# logger_Chad.net
KiCad netlist of a schematic drawn in EAGLE
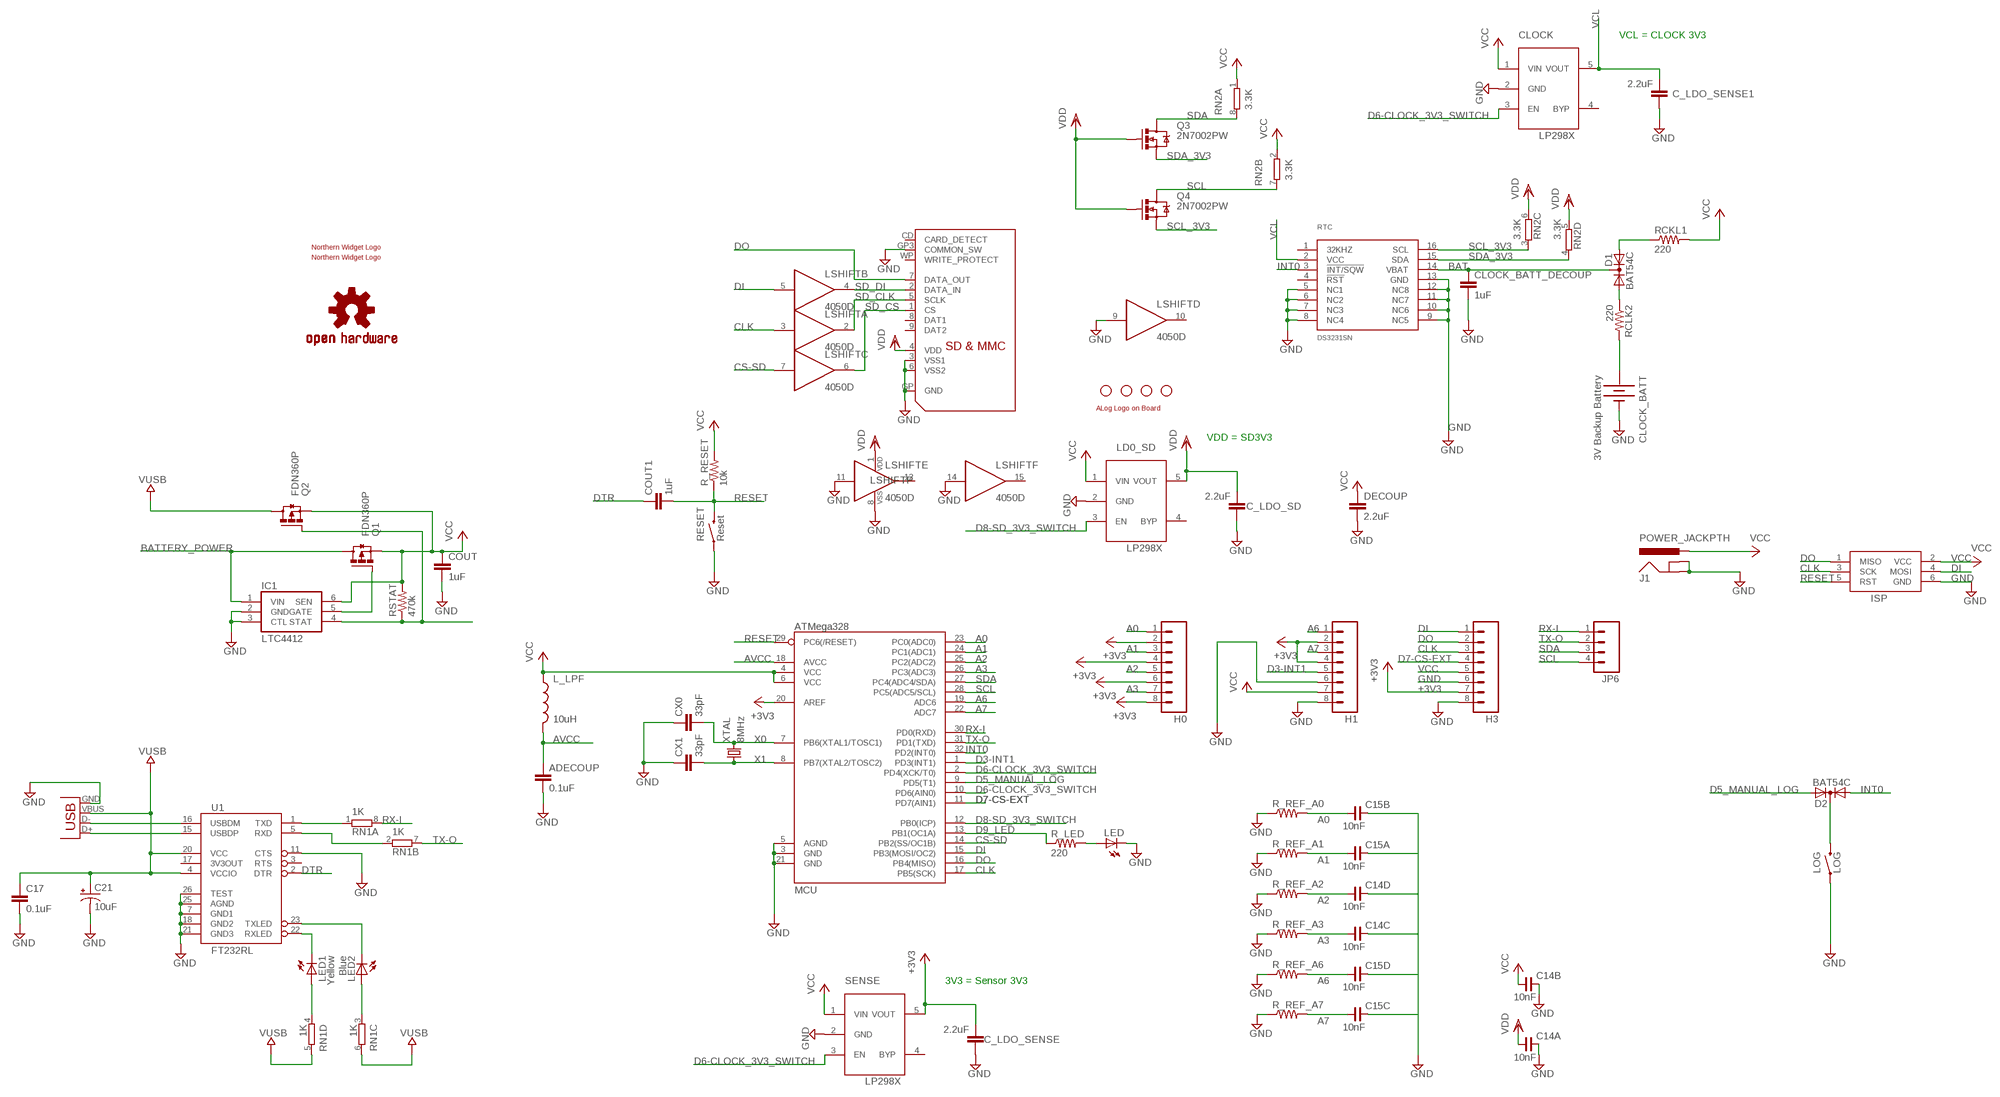
[diagram p0: schematic, sheet 1]

(export (version "E")
  (design (tool "Eeschema 10.0.6"))
  (components
    (comp (ref "ADECOUP")
      (value "0.1uF")
      (footprint "eagle-import:C0603")
      (libsource (lib "eagle-import") (part "resistor_C-EUC0603"))
    )
    (comp (ref "C14")
      (value "10nF")
      (footprint "eagle-import:CECJ-1206")
      (libsource (lib "eagle-import") (part "CCA_ECJ-1206"))
    )
    (comp (ref "C15")
      (value "10nF")
      (footprint "eagle-import:CECJ-1206")
      (libsource (lib "eagle-import") (part "CCA_ECJ-1206"))
    )
    (comp (ref "C17")
      (value "0.1uF")
      (footprint "eagle-import:C0603")
      (libsource (lib "eagle-import") (part "resistor_C-EUC0603"))
    )
    (comp (ref "C21")
      (value "10uF")
      (footprint "eagle-import:EIA3216")
      (libsource (lib "eagle-import") (part "CAP_POL1206"))
    )
    (comp (ref "CLOCK")
      (value "LP2985")
      (footprint "eagle-import:SOT23-5L")
      (libsource (lib "eagle-import") (part "LP298XS"))
    )
    (comp (ref "CLOCK_BATT")
      (value "3V Backup Battery")
      (footprint "eagle-import:BATTCON_12MM_PTH")
      (libsource (lib "eagle-import") (part "BATTERY12PTH"))
    )
    (comp (ref "CLOCK_BATT_DECOUP")
      (value "1uF")
      (footprint "eagle-import:C0603")
      (libsource (lib "eagle-import") (part "C-EUC0603"))
    )
    (comp (ref "COUT")
      (value "1uF")
      (footprint "eagle-import:C0603")
      (libsource (lib "eagle-import") (part "C-EUC0603"))
    )
    (comp (ref "COUT1")
      (value "1uF")
      (footprint "eagle-import:C0603")
      (libsource (lib "eagle-import") (part "C-EUC0603"))
    )
    (comp (ref "CX0")
      (value "33pF")
      (footprint "eagle-import:C0603")
      (libsource (lib "eagle-import") (part "resistor_C-EUC0603"))
    )
    (comp (ref "CX1")
      (value "33pF")
      (footprint "eagle-import:C0603")
      (libsource (lib "eagle-import") (part "resistor_C-EUC0603"))
    )
    (comp (ref "C_LDO_SD")
      (value "2.2uF")
      (footprint "eagle-import:C0603")
      (libsource (lib "eagle-import") (part "resistor_C-EUC0603"))
    )
    (comp (ref "C_LDO_SENSE")
      (value "2.2uF")
      (footprint "eagle-import:C0603")
      (libsource (lib "eagle-import") (part "resistor_C-EUC0603"))
    )
    (comp (ref "C_LDO_SENSE1")
      (value "2.2uF")
      (footprint "eagle-import:C0603")
      (libsource (lib "eagle-import") (part "resistor_C-EUC0603"))
    )
    (comp (ref "D1")
      (value "BAT54C")
      (footprint "eagle-import:SOT23C")
      (libsource (lib "eagle-import") (part "DIODE_AC-CA_"))
    )
    (comp (ref "D2")
      (value "BAT54C")
      (footprint "eagle-import:SOT23C")
      (libsource (lib "eagle-import") (part "DIODE_AC-CA_"))
    )
    (comp (ref "DECOUP")
      (value "2.2uF")
      (footprint "eagle-import:C0603")
      (libsource (lib "eagle-import") (part "resistor_C-EUC0603"))
    )
    (comp (ref "H0")
      (value "M083.5MM-8")
      (footprint "eagle-import:SCREWTERMINAL-3.5MM-8")
      (libsource (lib "eagle-import") (part "M083.5MM-8"))
    )
    (comp (ref "H1")
      (value "M083.5MM-8")
      (footprint "eagle-import:SCREWTERMINAL-3.5MM-8")
      (libsource (lib "eagle-import") (part "M083.5MM-8"))
    )
    (comp (ref "H3")
      (value "M083.5MM-8")
      (footprint "eagle-import:SCREWTERMINAL-3.5MM-8")
      (libsource (lib "eagle-import") (part "M083.5MM-8"))
    )
    (comp (ref "IC1")
      (value "LTC4412")
      (footprint "eagle-import:TSOT23-6")
      (libsource (lib "eagle-import") (part "LTC4412S6E"))
    )
    (comp (ref "ISP")
      (value "AVRISP-6")
      (footprint "eagle-import:AVRISP")
      (libsource (lib "eagle-import") (part "AVRISP-6"))
    )
    (comp (ref "J1")
      (value "POWER_JACKPTH")
      (footprint "eagle-import:POWER_JACK_PTH")
      (libsource (lib "eagle-import") (part "POWER_JACKPTH"))
    )
    (comp (ref "JP1")
      (value "STAND-OFF")
      (footprint "eagle-import:STAND-OFF")
      (libsource (lib "eagle-import") (part "STAND-OFF"))
    )
    (comp (ref "JP2")
      (value "STAND-OFF")
      (footprint "eagle-import:STAND-OFF")
      (libsource (lib "eagle-import") (part "STAND-OFF"))
    )
    (comp (ref "JP3")
      (value "STAND-OFF")
      (footprint "eagle-import:STAND-OFF")
      (libsource (lib "eagle-import") (part "STAND-OFF"))
    )
    (comp (ref "JP4")
      (value "STAND-OFF")
      (footprint "eagle-import:STAND-OFF")
      (libsource (lib "eagle-import") (part "STAND-OFF"))
    )
    (comp (ref "JP5")
      (value "USB-B")
      (footprint "eagle-import:USB-B-PTH")
      (libsource (lib "eagle-import") (part "USBPTH"))
    )
    (comp (ref "JP6")
      (value "M04SCREW")
      (footprint "eagle-import:SCREWTERMINAL-3.5MM-4")
      (libsource (lib "eagle-import") (part "M04SCREW"))
    )
    (comp (ref "LD0_SD")
      (value "LP2985")
      (footprint "eagle-import:SOT23-5L")
      (libsource (lib "eagle-import") (part "LP298XS"))
    )
    (comp (ref "LED")
      (value "LED3MM")
      (footprint "eagle-import:LED3MM")
      (libsource (lib "eagle-import") (part "LED3MM"))
    )
    (comp (ref "LED1")
      (value "Yellow")
      (footprint "eagle-import:LED-0603")
      (libsource (lib "eagle-import") (part "SparkFun-LED_LED0603"))
    )
    (comp (ref "LED2")
      (value "Blue")
      (footprint "eagle-import:LED-0603")
      (libsource (lib "eagle-import") (part "SparkFun-LED_LED0603"))
    )
    (comp (ref "LOG")
      (value "LOG")
      (footprint "eagle-import:TACTILE-PTH")
      (libsource (lib "eagle-import") (part "SWITCH-MOMENTARY-2PTH"))
    )
    (comp (ref "LOGO1")
      (value "OSHW-LOGOM")
      (footprint "eagle-import:OSHW-LOGO-M")
      (libsource (lib "eagle-import") (part "OSHW-LOGOM"))
    )
    (comp (ref "LSHIFT")
      (value "4050D")
      (footprint "eagle-import:SO16")
      (libsource (lib "eagle-import") (part "4050D"))
    )
    (comp (ref "L_LPF")
      (value "10uH")
      (footprint "eagle-import:0805")
      (libsource (lib "eagle-import") (part "INDUCTOR0805"))
    )
    (comp (ref "MCU")
      (value "ATMega328")
      (footprint "eagle-import:TQFP32-08")
      (libsource (lib "eagle-import") (part "ATMEGA168"))
    )
    (comp (ref "Q1")
      (value "FDN360P")
      (footprint "eagle-import:SUPER-SOT3")
      (libsource (lib "eagle-import") (part "FDN360P"))
    )
    (comp (ref "Q2")
      (value "FDN360P")
      (footprint "eagle-import:SUPER-SOT3")
      (libsource (lib "eagle-import") (part "FDN360P"))
    )
    (comp (ref "Q3")
      (value "2N7002PW")
      (footprint "eagle-import:SOT323")
      (libsource (lib "eagle-import") (part "MOSFET-NCHANNELSOT323"))
    )
    (comp (ref "Q4")
      (value "2N7002PW")
      (footprint "eagle-import:SOT323")
      (libsource (lib "eagle-import") (part "MOSFET-NCHANNELSOT323"))
    )
    (comp (ref "RCKL1")
      (value "220")
      (footprint "eagle-import:R0603")
      (libsource (lib "eagle-import") (part "R-US_R0603"))
    )
    (comp (ref "RCLK2")
      (value "220")
      (footprint "eagle-import:R0603")
      (libsource (lib "eagle-import") (part "R-US_R0603"))
    )
    (comp (ref "RESET")
      (value "Reset")
      (footprint "eagle-import:TACTILE-PTH")
      (libsource (lib "eagle-import") (part "SWITCH-MOMENTARY-2PTH"))
    )
    (comp (ref "RN1")
      (value "1K")
      (footprint "eagle-import:0603-ARC")
      (libsource (lib "eagle-import") (part "4R-N0603-ARC"))
    )
    (comp (ref "RN2")
      (value "3.3K")
      (footprint "eagle-import:0603-ARC")
      (libsource (lib "eagle-import") (part "4R-N0603-ARC"))
    )
    (comp (ref "RSTAT")
      (value "470k")
      (footprint "eagle-import:R0603")
      (libsource (lib "eagle-import") (part "R-US_R0603"))
    )
    (comp (ref "RTC")
      (value "DS3231SN")
      (footprint "eagle-import:SO16W")
      (libsource (lib "eagle-import") (part "DS3231SN"))
    )
    (comp (ref "R_LED")
      (value "220")
      (footprint "eagle-import:R0603")
      (libsource (lib "eagle-import") (part "resistor_R-US_R0603"))
    )
    (comp (ref "R_REF_A0")
      (value "R-US_0207/10")
      (footprint "eagle-import:0207_10")
      (libsource (lib "eagle-import") (part "resistor_R-US_0207/10"))
    )
    (comp (ref "R_REF_A1")
      (value "R-US_0207/10")
      (footprint "eagle-import:0207_10")
      (libsource (lib "eagle-import") (part "resistor_R-US_0207/10"))
    )
    (comp (ref "R_REF_A2")
      (value "R-US_0207/10")
      (footprint "eagle-import:0207_10")
      (libsource (lib "eagle-import") (part "resistor_R-US_0207/10"))
    )
    (comp (ref "R_REF_A3")
      (value "R-US_0207/10")
      (footprint "eagle-import:0207_10")
      (libsource (lib "eagle-import") (part "resistor_R-US_0207/10"))
    )
    (comp (ref "R_REF_A6")
      (value "R-US_0207/10")
      (footprint "eagle-import:0207_10")
      (libsource (lib "eagle-import") (part "resistor_R-US_0207/10"))
    )
    (comp (ref "R_REF_A7")
      (value "R-US_0207/10")
      (footprint "eagle-import:0207_10")
      (libsource (lib "eagle-import") (part "resistor_R-US_0207/10"))
    )
    (comp (ref "R_RESET")
      (value "10k")
      (footprint "eagle-import:R0603")
      (libsource (lib "eagle-import") (part "R-US_R0603"))
    )
    (comp (ref "SD")
      (value "SDMMC06132")
      (footprint "eagle-import:06132")
      (libsource (lib "eagle-import") (part "SDMMC06132"))
    )
    (comp (ref "SENSE")
      (value "LP2985")
      (footprint "eagle-import:SOT23-5L")
      (libsource (lib "eagle-import") (part "LP298XS"))
    )
    (comp (ref "U$1")
      (value "NWLOGO")
      (footprint "eagle-import:NWLOGO")
      (libsource (lib "eagle-import") (part "NWLOGO"))
    )
    (comp (ref "U$2")
      (value "ALOG_LOGO_V1_5.5MM")
      (footprint "eagle-import:ALOG_LOGO_V1_SMALL")
      (libsource (lib "eagle-import") (part "ALOG_LOGO_V1_5.5MM"))
    )
    (comp (ref "U$3")
      (value "NWLOGO_MED")
      (footprint "eagle-import:NWLOGO_MED")
      (libsource (lib "eagle-import") (part "NWLOGO_MED"))
    )
    (comp (ref "U1")
      (value "FT232RL")
      (footprint "eagle-import:SSOP28DB")
      (libsource (lib "eagle-import") (part "FT232RL-BASICSSOP"))
    )
    (comp (ref "XTAL")
      (value "8MHz")
      (footprint "eagle-import:HC49U-V")
      (libsource (lib "eagle-import") (part "CRYSTALHC49UV"))
    )
  )
  (nets
    (net (code "1") (name "+3V3") (class "Default")
      (node (ref "C_LDO_SENSE") (pin "2") (pinfunction "2_2") (pintype "passive"))
      (node (ref "H0") (pin "2") (pinfunction "2_2") (pintype "passive"))
      (node (ref "H0") (pin "4") (pinfunction "4_4") (pintype "passive"))
      (node (ref "H0") (pin "6") (pinfunction "6_6") (pintype "passive"))
      (node (ref "H0") (pin "8") (pinfunction "8_8") (pintype "passive"))
      (node (ref "H1") (pin "2") (pinfunction "2_2") (pintype "passive"))
      (node (ref "H1") (pin "4") (pinfunction "4_4") (pintype "passive"))
      (node (ref "H3") (pin "7") (pinfunction "7_7") (pintype "passive"))
      (node (ref "MCU") (pin "20") (pinfunction "AREF_20") (pintype "bidirectional"))
      (node (ref "SENSE") (pin "5") (pinfunction "VOUT_5") (pintype "bidirectional"))
    )
    (net (code "2") (name "/A0") (class "Default")
      (node (ref "C15") (pin "B1") (pinfunction "1_B1") (pintype "passive"))
      (node (ref "H0") (pin "1") (pinfunction "1_1") (pintype "passive"))
      (node (ref "MCU") (pin "23") (pinfunction "PC0(ADC0)_23") (pintype "bidirectional"))
      (node (ref "R_REF_A0") (pin "2") (pinfunction "2_2") (pintype "passive"))
    )
    (net (code "3") (name "/A1") (class "Default")
      (node (ref "C15") (pin "A1") (pinfunction "1_A1") (pintype "passive"))
      (node (ref "H0") (pin "3") (pinfunction "3_3") (pintype "passive"))
      (node (ref "MCU") (pin "24") (pinfunction "PC1(ADC1)_24") (pintype "bidirectional"))
      (node (ref "R_REF_A1") (pin "2") (pinfunction "2_2") (pintype "passive"))
    )
    (net (code "4") (name "/A2") (class "Default")
      (node (ref "C14") (pin "D1") (pinfunction "1_D1") (pintype "passive"))
      (node (ref "H0") (pin "5") (pinfunction "5_5") (pintype "passive"))
      (node (ref "MCU") (pin "25") (pinfunction "PC2(ADC2)_25") (pintype "bidirectional"))
      (node (ref "R_REF_A2") (pin "2") (pinfunction "2_2") (pintype "passive"))
    )
    (net (code "5") (name "/A3") (class "Default")
      (node (ref "C14") (pin "C1") (pinfunction "1_C1") (pintype "passive"))
      (node (ref "H0") (pin "7") (pinfunction "7_7") (pintype "passive"))
      (node (ref "MCU") (pin "26") (pinfunction "PC3(ADC3)_26") (pintype "bidirectional"))
      (node (ref "R_REF_A3") (pin "2") (pinfunction "2_2") (pintype "passive"))
    )
    (net (code "6") (name "/A6") (class "Default")
      (node (ref "C15") (pin "D1") (pinfunction "1_D1") (pintype "passive"))
      (node (ref "H1") (pin "1") (pinfunction "1_1") (pintype "passive"))
      (node (ref "MCU") (pin "19") (pinfunction "ADC6_19") (pintype "bidirectional"))
      (node (ref "R_REF_A6") (pin "2") (pinfunction "2_2") (pintype "passive"))
    )
    (net (code "7") (name "/A7") (class "Default")
      (node (ref "C15") (pin "C1") (pinfunction "1_C1") (pintype "passive"))
      (node (ref "H1") (pin "3") (pinfunction "3_3") (pintype "passive"))
      (node (ref "MCU") (pin "22") (pinfunction "ADC7_22") (pintype "bidirectional"))
      (node (ref "R_REF_A7") (pin "2") (pinfunction "2_2") (pintype "passive"))
    )
    (net (code "8") (name "/AVCC") (class "Default")
      (node (ref "ADECOUP") (pin "1") (pinfunction "1_1") (pintype "passive"))
      (node (ref "L_LPF") (pin "2") (pinfunction "2_2") (pintype "passive"))
      (node (ref "MCU") (pin "18") (pinfunction "AVCC_18") (pintype "bidirectional"))
    )
    (net (code "9") (name "/BAT") (class "Default")
      (node (ref "CLOCK_BATT_DECOUP") (pin "1") (pinfunction "1_1") (pintype "passive"))
      (node (ref "D1") (pin "3") (pinfunction "K_3") (pintype "passive"))
      (node (ref "RTC") (pin "14") (pinfunction "VBAT_14") (pintype "bidirectional"))
    )
    (net (code "10") (name "/BATTERY_POWER") (class "Default")
      (node (ref "IC1") (pin "1") (pinfunction "VIN_1") (pintype "input"))
      (node (ref "Q1") (pin "3") (pinfunction "D_3") (pintype "passive"))
    )
    (net (code "11") (name "/CLK") (class "Default")
      (node (ref "H3") (pin "3") (pinfunction "3_3") (pintype "passive"))
      (node (ref "ISP") (pin "3") (pinfunction "SCK_3") (pintype "output"))
      (node (ref "LSHIFT") (pin "3") (pinfunction "I_3") (pintype "input"))
      (node (ref "MCU") (pin "17") (pinfunction "PB5(SCK)_17") (pintype "bidirectional"))
    )
    (net (code "12") (name "/CS-SD") (class "Default")
      (node (ref "LSHIFT") (pin "7") (pinfunction "I_7") (pintype "input"))
      (node (ref "MCU") (pin "14") (pinfunction "PB2(SS/OC1B)_14") (pintype "bidirectional"))
    )
    (net (code "13") (name "/D3-INT1") (class "Default")
      (node (ref "H1") (pin "5") (pinfunction "5_5") (pintype "passive"))
      (node (ref "MCU") (pin "1") (pinfunction "PD3(INT1)_1") (pintype "bidirectional"))
    )
    (net (code "14") (name "/D5_MANUAL_LOG") (class "Default")
      (node (ref "D2") (pin "2") (pinfunction "A2_2") (pintype "passive"))
      (node (ref "MCU") (pin "9") (pinfunction "PD5(T1)_9") (pintype "bidirectional"))
    )
    (net (code "15") (name "/D6-CLOCK_3V3_SWITCH") (class "Default")
      (node (ref "CLOCK") (pin "3") (pinfunction "EN_3") (pintype "bidirectional"))
      (node (ref "MCU") (pin "10") (pinfunction "PD6(AIN0)_10") (pintype "bidirectional"))
      (node (ref "MCU") (pin "2") (pinfunction "PD4(XCK/T0)_2") (pintype "bidirectional"))
      (node (ref "SENSE") (pin "3") (pinfunction "EN_3") (pintype "bidirectional"))
    )
    (net (code "16") (name "/D7-CS-EXT") (class "Default")
      (node (ref "H3") (pin "4") (pinfunction "4_4") (pintype "passive"))
      (node (ref "MCU") (pin "11") (pinfunction "PD7(AIN1)_11") (pintype "bidirectional"))
    )
    (net (code "17") (name "/D8-SD_3V3_SWITCH") (class "Default")
      (node (ref "LD0_SD") (pin "3") (pinfunction "EN_3") (pintype "bidirectional"))
      (node (ref "MCU") (pin "12") (pinfunction "PB0(ICP)_12") (pintype "bidirectional"))
    )
    (net (code "18") (name "/D9_LED") (class "Default")
      (node (ref "MCU") (pin "13") (pinfunction "PB1(OC1A)_13") (pintype "bidirectional"))
      (node (ref "R_LED") (pin "1") (pinfunction "1_1") (pintype "passive"))
    )
    (net (code "19") (name "/DI") (class "Default")
      (node (ref "H3") (pin "1") (pinfunction "1_1") (pintype "passive"))
      (node (ref "ISP") (pin "4") (pinfunction "MOSI_4") (pintype "output"))
      (node (ref "LSHIFT") (pin "5") (pinfunction "I_5") (pintype "input"))
      (node (ref "MCU") (pin "15") (pinfunction "PB3(MOSI/OC2)_15") (pintype "bidirectional"))
    )
    (net (code "20") (name "/DO") (class "Default")
      (node (ref "H3") (pin "2") (pinfunction "2_2") (pintype "passive"))
      (node (ref "ISP") (pin "1") (pinfunction "MISO_1") (pintype "input"))
      (node (ref "MCU") (pin "16") (pinfunction "PB4(MISO)_16") (pintype "bidirectional"))
      (node (ref "SD") (pin "7") (pinfunction "DATA_OUT_7") (pintype "output"))
    )
    (net (code "21") (name "/DTR") (class "Default")
      (node (ref "COUT1") (pin "1") (pinfunction "1_1") (pintype "passive"))
      (node (ref "U1") (pin "2") (pinfunction "DTR_2") (pintype "bidirectional"))
    )
    (net (code "22") (name "/INT0") (class "Default")
      (node (ref "D2") (pin "1") (pinfunction "A1_1") (pintype "passive"))
      (node (ref "MCU") (pin "32") (pinfunction "PD2(INT0)_32") (pintype "bidirectional"))
      (node (ref "RTC") (pin "3") (pinfunction "~{INT/SQW}_3") (pintype "bidirectional"))
    )
    (net (code "23") (name "/RESET") (class "Default")
      (node (ref "COUT1") (pin "2") (pinfunction "2_2") (pintype "passive"))
      (node (ref "ISP") (pin "5") (pinfunction "RST_5") (pintype "output"))
      (node (ref "MCU") (pin "29") (pinfunction "PC6(/RESET)_29") (pintype "bidirectional"))
      (node (ref "RESET") (pin "3") (pinfunction "2_3") (pintype "passive"))
      (node (ref "R_RESET") (pin "1") (pinfunction "1_1") (pintype "passive"))
    )
    (net (code "24") (name "/RX-I") (class "Default")
      (node (ref "JP6") (pin "1") (pinfunction "1_1") (pintype "passive"))
      (node (ref "MCU") (pin "30") (pinfunction "PD0(RXD)_30") (pintype "bidirectional"))
      (node (ref "RN1") (pin "8") (pinfunction "2_8") (pintype "passive"))
    )
    (net (code "25") (name "/SCL") (class "Default")
      (node (ref "JP6") (pin "4") (pinfunction "4_4") (pintype "passive"))
      (node (ref "MCU") (pin "28") (pinfunction "PC5(ADC5/SCL)_28") (pintype "bidirectional"))
      (node (ref "Q4") (pin "3") (pinfunction "D_3") (pintype "passive"))
      (node (ref "RN2") (pin "7") (pinfunction "2_7") (pintype "passive"))
    )
    (net (code "26") (name "/SCL_3V3") (class "Default")
      (node (ref "Q4") (pin "2") (pinfunction "S_2") (pintype "passive"))
      (node (ref "RN2") (pin "3") (pinfunction "1_3") (pintype "passive"))
      (node (ref "RTC") (pin "16") (pinfunction "SCL_16") (pintype "bidirectional"))
    )
    (net (code "27") (name "/SDA") (class "Default")
      (node (ref "JP6") (pin "3") (pinfunction "3_3") (pintype "passive"))
      (node (ref "MCU") (pin "27") (pinfunction "PC4(ADC4/SDA)_27") (pintype "bidirectional"))
      (node (ref "Q3") (pin "3") (pinfunction "D_3") (pintype "passive"))
      (node (ref "RN2") (pin "8") (pinfunction "2_8") (pintype "passive"))
    )
    (net (code "28") (name "/SDA_3V3") (class "Default")
      (node (ref "Q3") (pin "2") (pinfunction "S_2") (pintype "passive"))
      (node (ref "RN2") (pin "4") (pinfunction "1_4") (pintype "passive"))
      (node (ref "RTC") (pin "15") (pinfunction "SDA_15") (pintype "bidirectional"))
    )
    (net (code "29") (name "/SD_CLK") (class "Default")
      (node (ref "LSHIFT") (pin "2") (pinfunction "O_2") (pintype "output"))
      (node (ref "SD") (pin "5") (pinfunction "SCLK_5") (pintype "input"))
    )
    (net (code "30") (name "/SD_CS") (class "Default")
      (node (ref "LSHIFT") (pin "6") (pinfunction "O_6") (pintype "output"))
      (node (ref "SD") (pin "1") (pinfunction "CS_1") (pintype "input"))
    )
    (net (code "31") (name "/SD_DI") (class "Default")
      (node (ref "LSHIFT") (pin "4") (pinfunction "O_4") (pintype "output"))
      (node (ref "SD") (pin "2") (pinfunction "DATA_IN_2") (pintype "input"))
    )
    (net (code "32") (name "/TX-O") (class "Default")
      (node (ref "JP6") (pin "2") (pinfunction "2_2") (pintype "passive"))
      (node (ref "MCU") (pin "31") (pinfunction "PD1(TXD)_31") (pintype "bidirectional"))
      (node (ref "RN1") (pin "7") (pinfunction "2_7") (pintype "passive"))
    )
    (net (code "33") (name "/VCL") (class "Default")
      (node (ref "CLOCK") (pin "5") (pinfunction "VOUT_5") (pintype "bidirectional"))
      (node (ref "C_LDO_SENSE1") (pin "2") (pinfunction "2_2") (pintype "passive"))
      (node (ref "RTC") (pin "2") (pinfunction "VCC_2") (pintype "bidirectional"))
    )
    (net (code "34") (name "/X0") (class "Default")
      (node (ref "CX0") (pin "2") (pinfunction "2_2") (pintype "passive"))
      (node (ref "MCU") (pin "7") (pinfunction "PB6(XTAL1/TOSC1)_7") (pintype "bidirectional"))
      (node (ref "XTAL") (pin "2") (pinfunction "2_2") (pintype "passive"))
    )
    (net (code "35") (name "/X1") (class "Default")
      (node (ref "CX1") (pin "2") (pinfunction "2_2") (pintype "passive"))
      (node (ref "MCU") (pin "8") (pinfunction "PB7(XTAL2/TOSC2)_8") (pintype "bidirectional"))
      (node (ref "XTAL") (pin "1") (pinfunction "1_1") (pintype "passive"))
    )
    (net (code "36") (name "GND") (class "Default")
      (node (ref "ADECOUP") (pin "2") (pinfunction "2_2") (pintype "passive"))
      (node (ref "C14") (pin "A2") (pinfunction "2_A2") (pintype "passive"))
      (node (ref "C14") (pin "B2") (pinfunction "2_B2") (pintype "passive"))
      (node (ref "C14") (pin "C2") (pinfunction "2_C2") (pintype "passive"))
      (node (ref "C14") (pin "D2") (pinfunction "2_D2") (pintype "passive"))
      (node (ref "C15") (pin "A2") (pinfunction "2_A2") (pintype "passive"))
      (node (ref "C15") (pin "B2") (pinfunction "2_B2") (pintype "passive"))
      (node (ref "C15") (pin "C2") (pinfunction "2_C2") (pintype "passive"))
      (node (ref "C15") (pin "D2") (pinfunction "2_D2") (pintype "passive"))
      (node (ref "C17") (pin "2") (pinfunction "2_2") (pintype "passive"))
      (node (ref "C21") (pin "C") (pinfunction "-_C") (pintype "passive"))
      (node (ref "CLOCK") (pin "2") (pinfunction "GND_2") (pintype "bidirectional"))
      (node (ref "CLOCK_BATT") (pin "GND") (pinfunction "-_GND") (pintype "power_in"))
      (node (ref "CLOCK_BATT_DECOUP") (pin "2") (pinfunction "2_2") (pintype "passive"))
      (node (ref "COUT") (pin "2") (pinfunction "2_2") (pintype "passive"))
      (node (ref "CX0") (pin "1") (pinfunction "1_1") (pintype "passive"))
      (node (ref "CX1") (pin "1") (pinfunction "1_1") (pintype "passive"))
      (node (ref "C_LDO_SD") (pin "1") (pinfunction "1_1") (pintype "passive"))
      (node (ref "C_LDO_SENSE") (pin "1") (pinfunction "1_1") (pintype "passive"))
      (node (ref "C_LDO_SENSE1") (pin "1") (pinfunction "1_1") (pintype "passive"))
      (node (ref "DECOUP") (pin "2") (pinfunction "2_2") (pintype "passive"))
      (node (ref "H1") (pin "6") (pinfunction "6_6") (pintype "passive"))
      (node (ref "H1") (pin "8") (pinfunction "8_8") (pintype "passive"))
      (node (ref "H3") (pin "6") (pinfunction "6_6") (pintype "passive"))
      (node (ref "H3") (pin "8") (pinfunction "8_8") (pintype "passive"))
      (node (ref "IC1") (pin "2") (pinfunction "GND_2") (pintype "passive"))
      (node (ref "IC1") (pin "3") (pinfunction "CTL_3") (pintype "input"))
      (node (ref "ISP") (pin "6") (pinfunction "GND_6") (pintype "power_in"))
      (node (ref "J1") (pin "GND") (pinfunction "GND_GND") (pintype "bidirectional"))
      (node (ref "J1") (pin "GNDBREAK") (pinfunction "GNDBREAK_GNDBREAK") (pintype "bidirectional"))
      (node (ref "JP5") (pin "GND") (pinfunction "GND_GND") (pintype "bidirectional"))
      (node (ref "LD0_SD") (pin "2") (pinfunction "GND_2") (pintype "bidirectional"))
      (node (ref "LED") (pin "K") (pinfunction "C_K") (pintype "passive"))
      (node (ref "LOG") (pin "1") (pinfunction "1_1") (pintype "passive"))
      (node (ref "LSHIFT") (pin "11") (pinfunction "I_11") (pintype "input"))
      (node (ref "LSHIFT") (pin "14") (pinfunction "I_14") (pintype "input"))
      (node (ref "LSHIFT") (pin "8") (pinfunction "VSS_8") (pintype "power_in"))
      (node (ref "LSHIFT") (pin "9") (pinfunction "I_9") (pintype "input"))
      (node (ref "MCU") (pin "21") (pinfunction "GND_21") (pintype "bidirectional"))
      (node (ref "MCU") (pin "3") (pinfunction "GND_3") (pintype "bidirectional"))
      (node (ref "MCU") (pin "5") (pinfunction "AGND_5") (pintype "bidirectional"))
      (node (ref "RESET") (pin "1") (pinfunction "1_1") (pintype "passive"))
      (node (ref "RTC") (pin "10") (pinfunction "NC6_10") (pintype "bidirectional"))
      (node (ref "RTC") (pin "11") (pinfunction "NC7_11") (pintype "bidirectional"))
      (node (ref "RTC") (pin "12") (pinfunction "NC8_12") (pintype "bidirectional"))
      (node (ref "RTC") (pin "13") (pinfunction "GND_13") (pintype "bidirectional"))
      (node (ref "RTC") (pin "5") (pinfunction "NC1_5") (pintype "bidirectional"))
      (node (ref "RTC") (pin "6") (pinfunction "NC2_6") (pintype "bidirectional"))
      (node (ref "RTC") (pin "7") (pinfunction "NC3_7") (pintype "bidirectional"))
      (node (ref "RTC") (pin "8") (pinfunction "NC4_8") (pintype "bidirectional"))
      (node (ref "RTC") (pin "9") (pinfunction "NC5_9") (pintype "bidirectional"))
      (node (ref "R_REF_A0") (pin "1") (pinfunction "1_1") (pintype "passive"))
      (node (ref "R_REF_A1") (pin "1") (pinfunction "1_1") (pintype "passive"))
      (node (ref "R_REF_A2") (pin "1") (pinfunction "1_1") (pintype "passive"))
      (node (ref "R_REF_A3") (pin "1") (pinfunction "1_1") (pintype "passive"))
      (node (ref "R_REF_A6") (pin "1") (pinfunction "1_1") (pintype "passive"))
      (node (ref "R_REF_A7") (pin "1") (pinfunction "1_1") (pintype "passive"))
      (node (ref "SD") (pin "3") (pinfunction "VSS1_3") (pintype "power_in"))
      (node (ref "SD") (pin "6") (pinfunction "VSS2_6") (pintype "power_in"))
      (node (ref "SD") (pin "GP") (pinfunction "GND_GP") (pintype "power_in"))
      (node (ref "SD") (pin "GP3") (pinfunction "COMMON_SW_GP3") (pintype "passive"))
      (node (ref "SENSE") (pin "2") (pinfunction "GND_2") (pintype "bidirectional"))
      (node (ref "U1") (pin "11") (pinfunction "CTS_11") (pintype "bidirectional"))
      (node (ref "U1") (pin "18") (pinfunction "GND2_18") (pintype "power_in"))
      (node (ref "U1") (pin "21") (pinfunction "GND3_21") (pintype "power_in"))
      (node (ref "U1") (pin "25") (pinfunction "AGND_25") (pintype "power_in"))
      (node (ref "U1") (pin "26") (pinfunction "TEST_26") (pintype "input"))
      (node (ref "U1") (pin "7") (pinfunction "GND1_7") (pintype "power_in"))
    )
    (net (code "37") (name "Net-(CLOCK_BATT-+)") (class "Default")
      (node (ref "CLOCK_BATT") (pin "VCC@1") (pinfunction "+_VCC@1") (pintype "power_in"))
      (node (ref "RCLK2") (pin "2") (pinfunction "2_2") (pintype "passive"))
    )
    (net (code "38") (name "Net-(D1-A1)") (class "Default")
      (node (ref "D1") (pin "1") (pinfunction "A1_1") (pintype "passive"))
      (node (ref "RCLK2") (pin "1") (pinfunction "1_1") (pintype "passive"))
    )
    (net (code "39") (name "Net-(D1-A2)") (class "Default")
      (node (ref "D1") (pin "2") (pinfunction "A2_2") (pintype "passive"))
      (node (ref "RCKL1") (pin "1") (pinfunction "1_1") (pintype "passive"))
    )
    (net (code "40") (name "Net-(D2-K)") (class "Default")
      (node (ref "D2") (pin "3") (pinfunction "K_3") (pintype "passive"))
      (node (ref "LOG") (pin "3") (pinfunction "2_3") (pintype "passive"))
    )
    (net (code "41") (name "Net-(IC1-GATE)") (class "Default")
      (node (ref "IC1") (pin "5") (pinfunction "GATE_5") (pintype "output"))
      (node (ref "Q1") (pin "1") (pinfunction "G_1") (pintype "passive"))
    )
    (net (code "42") (name "Net-(IC1-STAT)") (class "Default")
      (node (ref "IC1") (pin "4") (pinfunction "STAT_4") (pintype "open_collector"))
      (node (ref "Q2") (pin "1") (pinfunction "G_1") (pintype "passive"))
      (node (ref "RSTAT") (pin "1") (pinfunction "1_1") (pintype "passive"))
    )
    (net (code "43") (name "Net-(LED-PadA)") (class "Default")
      (node (ref "LED") (pin "A") (pinfunction "A_A") (pintype "passive"))
      (node (ref "R_LED") (pin "2") (pinfunction "2_2") (pintype "passive"))
    )
    (net (code "44") (name "Net-(RN1B-1)") (class "Default")
      (node (ref "RN1") (pin "2") (pinfunction "1_2") (pintype "passive"))
      (node (ref "U1") (pin "5") (pinfunction "RXD_5") (pintype "input"))
    )
    (net (code "45") (name "Net-(RN1C-1)") (class "Default")
      (node (ref "LED2") (pin "A") (pinfunction "A_A") (pintype "passive"))
      (node (ref "RN1") (pin "3") (pinfunction "1_3") (pintype "passive"))
    )
    (net (code "46") (name "Net-(RN1D-1)") (class "Default")
      (node (ref "LED1") (pin "A") (pinfunction "A_A") (pintype "passive"))
      (node (ref "RN1") (pin "4") (pinfunction "1_4") (pintype "passive"))
    )
    (net (code "47") (name "Net-(U1-RXLED)") (class "Default")
      (node (ref "LED1") (pin "C") (pinfunction "C_C") (pintype "passive"))
      (node (ref "U1") (pin "22") (pinfunction "RXLED_22") (pintype "bidirectional"))
    )
    (net (code "48") (name "Net-(U1-TXD)") (class "Default")
      (node (ref "RN1") (pin "1") (pinfunction "1_1") (pintype "passive"))
      (node (ref "U1") (pin "1") (pinfunction "TXD_1") (pintype "output"))
    )
    (net (code "49") (name "Net-(U1-TXLED)") (class "Default")
      (node (ref "LED2") (pin "C") (pinfunction "C_C") (pintype "passive"))
      (node (ref "U1") (pin "23") (pinfunction "TXLED_23") (pintype "bidirectional"))
    )
    (net (code "50") (name "Net-(U1-USBDM)") (class "Default")
      (node (ref "JP5") (pin "D-") (pinfunction "D-_D-") (pintype "bidirectional"))
      (node (ref "U1") (pin "16") (pinfunction "USBDM_16") (pintype "bidirectional"))
    )
    (net (code "51") (name "Net-(U1-USBDP)") (class "Default")
      (node (ref "JP5") (pin "D+") (pinfunction "D+_D+") (pintype "bidirectional"))
      (node (ref "U1") (pin "15") (pinfunction "USBDP_15") (pintype "bidirectional"))
    )
    (net (code "52") (name "VCC") (class "Default")
      (node (ref "C14") (pin "B1") (pinfunction "1_B1") (pintype "passive"))
      (node (ref "CLOCK") (pin "1") (pinfunction "VIN_1") (pintype "bidirectional"))
      (node (ref "COUT") (pin "1") (pinfunction "1_1") (pintype "passive"))
      (node (ref "DECOUP") (pin "1") (pinfunction "1_1") (pintype "passive"))
      (node (ref "H1") (pin "7") (pinfunction "7_7") (pintype "passive"))
      (node (ref "H3") (pin "5") (pinfunction "5_5") (pintype "passive"))
      (node (ref "IC1") (pin "6") (pinfunction "SEN_6") (pintype "input"))
      (node (ref "ISP") (pin "2") (pinfunction "VCC_2") (pintype "power_in"))
      (node (ref "J1") (pin "PWR") (pinfunction "PWR_PWR") (pintype "bidirectional"))
      (node (ref "LD0_SD") (pin "1") (pinfunction "VIN_1") (pintype "bidirectional"))
      (node (ref "L_LPF") (pin "1") (pinfunction "1_1") (pintype "passive"))
      (node (ref "MCU") (pin "4") (pinfunction "VCC_4") (pintype "bidirectional"))
      (node (ref "MCU") (pin "6") (pinfunction "VCC_6") (pintype "bidirectional"))
      (node (ref "Q1") (pin "2") (pinfunction "S_2") (pintype "passive"))
      (node (ref "Q2") (pin "2") (pinfunction "S_2") (pintype "passive"))
      (node (ref "RCKL1") (pin "2") (pinfunction "2_2") (pintype "passive"))
      (node (ref "RN2") (pin "1") (pinfunction "1_1") (pintype "passive"))
      (node (ref "RN2") (pin "2") (pinfunction "1_2") (pintype "passive"))
      (node (ref "RSTAT") (pin "2") (pinfunction "2_2") (pintype "passive"))
      (node (ref "R_RESET") (pin "2") (pinfunction "2_2") (pintype "passive"))
      (node (ref "SENSE") (pin "1") (pinfunction "VIN_1") (pintype "bidirectional"))
    )
    (net (code "53") (name "VDD") (class "Default")
      (node (ref "C14") (pin "A1") (pinfunction "1_A1") (pintype "passive"))
      (node (ref "C_LDO_SD") (pin "2") (pinfunction "2_2") (pintype "passive"))
      (node (ref "LD0_SD") (pin "5") (pinfunction "VOUT_5") (pintype "bidirectional"))
      (node (ref "LSHIFT") (pin "1") (pinfunction "VDD_1") (pintype "power_in"))
      (node (ref "Q3") (pin "1") (pinfunction "G_1") (pintype "passive"))
      (node (ref "Q4") (pin "1") (pinfunction "G_1") (pintype "passive"))
      (node (ref "RN2") (pin "5") (pinfunction "2_5") (pintype "passive"))
      (node (ref "RN2") (pin "6") (pinfunction "2_6") (pintype "passive"))
      (node (ref "SD") (pin "4") (pinfunction "VDD_4") (pintype "power_in"))
    )
    (net (code "54") (name "VUSB") (class "Default")
      (node (ref "C17") (pin "1") (pinfunction "1_1") (pintype "passive"))
      (node (ref "C21") (pin "A") (pinfunction "+_A") (pintype "passive"))
      (node (ref "JP5") (pin "VBUS") (pinfunction "VBUS_VBUS") (pintype "bidirectional"))
      (node (ref "Q2") (pin "3") (pinfunction "D_3") (pintype "passive"))
      (node (ref "RN1") (pin "5") (pinfunction "2_5") (pintype "passive"))
      (node (ref "RN1") (pin "6") (pinfunction "2_6") (pintype "passive"))
      (node (ref "U1") (pin "20") (pinfunction "VCC_20") (pintype "power_in"))
      (node (ref "U1") (pin "4") (pinfunction "VCCIO_4") (pintype "power_in"))
    )
    (net (code "55") (name "unconnected-(CLOCK-BYP-Pad4)") (class "Default")
      (node (ref "CLOCK") (pin "4") (pinfunction "BYP_4") (pintype "bidirectional"))
    )
    (net (code "56") (name "unconnected-(LD0_SD-BYP-Pad4)") (class "Default")
      (node (ref "LD0_SD") (pin "4") (pinfunction "BYP_4") (pintype "bidirectional"))
    )
    (net (code "57") (name "unconnected-(LSHIFTD-O-Pad10)") (class "Default")
      (node (ref "LSHIFT") (pin "10") (pinfunction "O_10") (pintype "output"))
    )
    (net (code "58") (name "unconnected-(LSHIFTE-O-Pad12)") (class "Default")
      (node (ref "LSHIFT") (pin "12") (pinfunction "O_12") (pintype "output"))
    )
    (net (code "59") (name "unconnected-(LSHIFTF-O-Pad15)") (class "Default")
      (node (ref "LSHIFT") (pin "15") (pinfunction "O_15") (pintype "output"))
    )
    (net (code "60") (name "unconnected-(RTC-32KHZ-Pad1)") (class "Default")
      (node (ref "RTC") (pin "1") (pinfunction "32KHZ_1") (pintype "bidirectional"))
    )
    (net (code "61") (name "unconnected-(RTC-~{RST}-Pad4)") (class "Default")
      (node (ref "RTC") (pin "4") (pinfunction "~{RST}_4") (pintype "bidirectional"))
    )
    (net (code "62") (name "unconnected-(SD-CARD_DETECT-PadCD)") (class "Default")
      (node (ref "SD") (pin "CD") (pinfunction "CARD_DETECT_CD") (pintype "passive"))
    )
    (net (code "63") (name "unconnected-(SD-DAT1-Pad8)") (class "Default")
      (node (ref "SD") (pin "8") (pinfunction "DAT1_8") (pintype "bidirectional"))
    )
    (net (code "64") (name "unconnected-(SD-DAT2-Pad9)") (class "Default")
      (node (ref "SD") (pin "9") (pinfunction "DAT2_9") (pintype "bidirectional"))
    )
    (net (code "65") (name "unconnected-(SD-WRITE_PROTECT-PadWP)") (class "Default")
      (node (ref "SD") (pin "WP") (pinfunction "WRITE_PROTECT_WP") (pintype "passive"))
    )
    (net (code "66") (name "unconnected-(SENSE-BYP-Pad4)") (class "Default")
      (node (ref "SENSE") (pin "4") (pinfunction "BYP_4") (pintype "bidirectional"))
    )
    (net (code "67") (name "unconnected-(U1-3V3OUT-Pad17)") (class "Default")
      (node (ref "U1") (pin "17") (pinfunction "3V3OUT_17") (pintype "output"))
    )
    (net (code "68") (name "unconnected-(U1-RTS-Pad3)") (class "Default")
      (node (ref "U1") (pin "3") (pinfunction "RTS_3") (pintype "bidirectional"))
    )
  )
)
